# LED_Chaser.net
KiCad netlist of a schematic drawn in Altium Designer
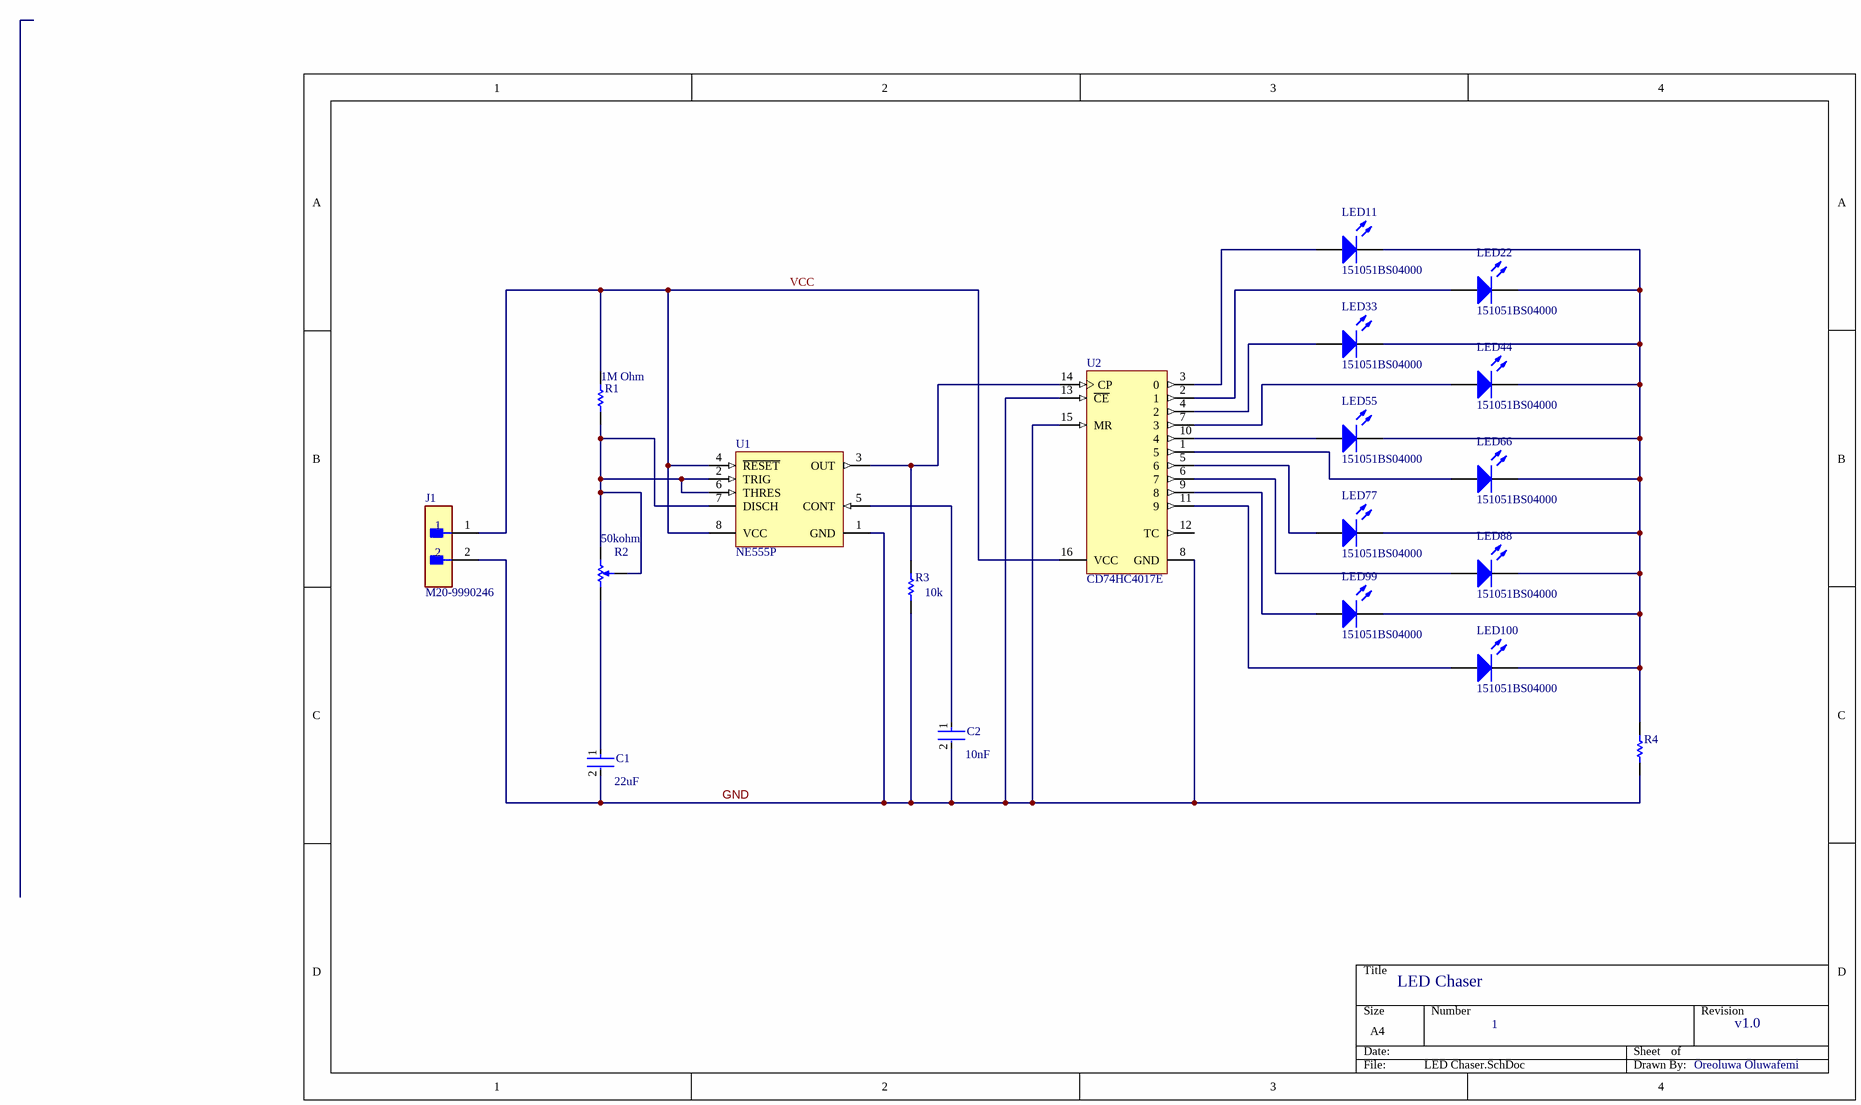
[diagram p0: LED Chaser.SchDoc]

(export (version "E")
  (design (tool "Eeschema 10.0.6"))
  (components
    (comp (ref "C1")
      (value "RCER71E226MWM1H03A")
      (footprint "FP-RCEWM1-MFG")
      (description "CAP CER 22UF 25V X7R RADIAL")
      (fields (field (name "CAPACITANCE") "22uF") (field (name "TOLERANCE") "20%"))
      (libsource (lib "Altium Content Vault") (part "02cd4be3c70576c341d710602a673aa"))
    )
    (comp (ref "C2")
      (value "RCER71E226MWM1H03A")
      (footprint "FP-RCEWM1-MFG")
      (description "CAP CER 22UF 25V X7R RADIAL")
      (fields (field (name "CAPACITANCE") "10nF") (field (name "TOLERANCE") "20%"))
      (libsource (lib "Altium Content Vault") (part "02cd4be3c70576c341d710602a673aa"))
    )
    (comp (ref "J1")
      (value "M20-9990246")
      (footprint "FP-M20-9990246-MFG")
      (description "CONN HEADER VERT 2POS 2.54MM")
      (fields
        (field (name "OCTOPART") "https://octopart.com/m20-9990246-harwin-2590635")
        (field (name "MANUFACTURER") "Harwin")
      )
      (libsource (lib "Altium Content Vault") (part "3bc925449376181038e59eaffc5286c"))
    )
    (comp (ref "LED11")
      (value "151051BS04000")
      (footprint "Type 5mm")
      (description "THT LED round mono-color color lens, WL-TMRW, Blue")
      (fields (field (name "MANUFACTURER") "Wuerth Elektronik"))
      (libsource (lib "Altium Content Vault") (part "WE-LED_K1A2-2"))
    )
    (comp (ref "LED22")
      (value "151051BS04000")
      (footprint "Type 5mm")
      (description "THT LED round mono-color color lens, WL-TMRW, Blue")
      (fields (field (name "MANUFACTURER") "Wuerth Elektronik"))
      (libsource (lib "Altium Content Vault") (part "WE-LED_K1A2-2"))
    )
    (comp (ref "LED33")
      (value "151051BS04000")
      (footprint "Type 5mm")
      (description "THT LED round mono-color color lens, WL-TMRW, Blue")
      (fields (field (name "MANUFACTURER") "Wuerth Elektronik"))
      (libsource (lib "Altium Content Vault") (part "WE-LED_K1A2-2"))
    )
    (comp (ref "LED44")
      (value "151051BS04000")
      (footprint "Type 5mm")
      (description "THT LED round mono-color color lens, WL-TMRW, Blue")
      (fields (field (name "MANUFACTURER") "Wuerth Elektronik"))
      (libsource (lib "Altium Content Vault") (part "WE-LED_K1A2-2"))
    )
    (comp (ref "LED55")
      (value "151051BS04000")
      (footprint "Type 5mm")
      (description "THT LED round mono-color color lens, WL-TMRW, Blue")
      (fields (field (name "MANUFACTURER") "Wuerth Elektronik"))
      (libsource (lib "Altium Content Vault") (part "WE-LED_K1A2-2"))
    )
    (comp (ref "LED66")
      (value "151051BS04000")
      (footprint "Type 5mm")
      (description "THT LED round mono-color color lens, WL-TMRW, Blue")
      (fields (field (name "MANUFACTURER") "Wuerth Elektronik"))
      (libsource (lib "Altium Content Vault") (part "WE-LED_K1A2-2"))
    )
    (comp (ref "LED77")
      (value "151051BS04000")
      (footprint "Type 5mm")
      (description "THT LED round mono-color color lens, WL-TMRW, Blue")
      (fields (field (name "MANUFACTURER") "Wuerth Elektronik"))
      (libsource (lib "Altium Content Vault") (part "WE-LED_K1A2-2"))
    )
    (comp (ref "LED88")
      (value "151051BS04000")
      (footprint "Type 5mm")
      (description "THT LED round mono-color color lens, WL-TMRW, Blue")
      (fields (field (name "MANUFACTURER") "Wuerth Elektronik"))
      (libsource (lib "Altium Content Vault") (part "WE-LED_K1A2-2"))
    )
    (comp (ref "LED99")
      (value "151051BS04000")
      (footprint "Type 5mm")
      (description "THT LED round mono-color color lens, WL-TMRW, Blue")
      (fields (field (name "MANUFACTURER") "Wuerth Elektronik"))
      (libsource (lib "Altium Content Vault") (part "WE-LED_K1A2-2"))
    )
    (comp (ref "LED100")
      (value "151051BS04000")
      (footprint "Type 5mm")
      (description "THT LED round mono-color color lens, WL-TMRW, Blue")
      (fields (field (name "MANUFACTURER") "Wuerth Elektronik"))
      (libsource (lib "Altium Content Vault") (part "WE-LED_K1A2-2"))
    )
    (comp (ref "R1")
      (value "MFR-25FBF52-100K")
      (footprint "RESA60-630X240")
      (description "Axial Resistor, 100 KOhm, +/- 1%, 0.25 W, -55 to 155 degC, 2-Pin THD, RoHS, Bulk")
      (fields (field (name "RESISTANCE") "1M Ohm") (field (name "TOLERANCE") "1%"))
      (libsource (lib "Altium Content Vault") (part "RES-2"))
    )
    (comp (ref "R2")
      (value "3313J-1-503E")
      (footprint "BOUR-3313J-1_V")
      (fields (field (name "MANUFACTURER") "Bourns") (field (name "TRACK RESISTANCE") "50kohm"))
      (libsource (lib "Altium Content Vault") (part "RES-ADJ-3_A"))
    )
    (comp (ref "R3")
      (value "OD103JE")
      (footprint "OMTE-RES7X2.5-2")
      (fields
        (field (name "RESISTANCE (OHMS)") "10k")
        (field (name "TOLERANCE") "±5%")
        (field (name "MANUFACTURER") "Ohmite")
      )
      (libsource (lib "Altium Content Vault") (part "RES-2"))
    )
    (comp (ref "R4")
      (value "OD103JE")
      (footprint "OMTE-RES7X2.5-2")
      (fields (field (name "TOLERANCE") "±5%") (field (name "MANUFACTURER") "Ohmite"))
      (libsource (lib "Altium Content Vault") (part "RES-2"))
    )
    (comp (ref "U1")
      (value "NE555P")
      (footprint "P0008A")
      (description "Precision Timer, 4.5 to 16 V, 0 to 70 degC, 8-Pin DIP, Pb-Free, Tube")
      (fields (field (name "MANUFACTURER") "TexasInstruments"))
      (libsource (lib "Altium Content Vault") (part "TI-NE555-P8"))
    )
    (comp (ref "U2")
      (value "CD74HC4017E")
      (footprint "N0016A")
      (description "High Speed CMOS Logic Decade Counter/Divider with 10 Decoded Outputs, N0016A, TUBE")
      (fields
        (field (name "GENERIC PART NUMBER") "CD74HC4017")
        (field (name "MANUFACTURER") "Texas Instruments")
      )
      (libsource (lib "Altium Content Vault") (part "TI-CD74HC4017-16"))
    )
  )
  (nets
    (net (code "1") (name "/GND") (class "Default")
      (node (ref "C1") (pin "2") (pinfunction "2_2") (pintype "passive"))
      (node (ref "C2") (pin "2") (pinfunction "2_2") (pintype "passive"))
      (node (ref "J1") (pin "2") (pinfunction "2_2") (pintype "passive"))
      (node (ref "R3") (pin "1") (pinfunction "1_1") (pintype "passive"))
      (node (ref "R4") (pin "1") (pinfunction "1_1") (pintype "passive"))
      (node (ref "U1") (pin "1") (pinfunction "GND_1") (pintype "power_in"))
      (node (ref "U2") (pin "13") (pinfunction "~{CE}_13") (pintype "input"))
      (node (ref "U2") (pin "15") (pinfunction "MR_15") (pintype "input"))
      (node (ref "U2") (pin "8") (pinfunction "GND_8") (pintype "power_in"))
    )
    (net (code "2") (name "/VCC") (class "Default")
      (node (ref "J1") (pin "1") (pinfunction "1_1") (pintype "passive"))
      (node (ref "R1") (pin "2") (pinfunction "2_2") (pintype "passive"))
      (node (ref "U1") (pin "4") (pinfunction "~{RESET}_4") (pintype "input"))
      (node (ref "U1") (pin "8") (pinfunction "VCC_8") (pintype "power_in"))
      (node (ref "U2") (pin "16") (pinfunction "VCC_16") (pintype "power_in"))
    )
    (net (code "3") (name "Net-(C1-Pad1)") (class "Default")
      (node (ref "C1") (pin "1") (pinfunction "1_1") (pintype "passive"))
      (node (ref "R2") (pin "1") (pinfunction "1_1") (pintype "passive"))
    )
    (net (code "4") (name "Net-(LED11-A)") (class "Default")
      (node (ref "LED11") (pin "2") (pinfunction "A_2") (pintype "passive"))
      (node (ref "U2") (pin "3") (pinfunction "0_3") (pintype "output"))
    )
    (net (code "5") (name "Net-(LED22-A)") (class "Default")
      (node (ref "LED22") (pin "2") (pinfunction "A_2") (pintype "passive"))
      (node (ref "U2") (pin "2") (pinfunction "1_2") (pintype "output"))
    )
    (net (code "6") (name "Net-(LED33-A)") (class "Default")
      (node (ref "LED33") (pin "2") (pinfunction "A_2") (pintype "passive"))
      (node (ref "U2") (pin "4") (pinfunction "2_4") (pintype "output"))
    )
    (net (code "7") (name "Net-(LED44-A)") (class "Default")
      (node (ref "LED44") (pin "2") (pinfunction "A_2") (pintype "passive"))
      (node (ref "U2") (pin "7") (pinfunction "3_7") (pintype "output"))
    )
    (net (code "8") (name "Net-(LED55-A)") (class "Default")
      (node (ref "LED55") (pin "2") (pinfunction "A_2") (pintype "passive"))
      (node (ref "U2") (pin "10") (pinfunction "4_10") (pintype "output"))
    )
    (net (code "9") (name "Net-(LED66-A)") (class "Default")
      (node (ref "LED66") (pin "2") (pinfunction "A_2") (pintype "passive"))
      (node (ref "U2") (pin "1") (pinfunction "5_1") (pintype "output"))
    )
    (net (code "10") (name "Net-(LED77-A)") (class "Default")
      (node (ref "LED77") (pin "2") (pinfunction "A_2") (pintype "passive"))
      (node (ref "U2") (pin "5") (pinfunction "6_5") (pintype "output"))
    )
    (net (code "11") (name "Net-(LED88-A)") (class "Default")
      (node (ref "LED88") (pin "2") (pinfunction "A_2") (pintype "passive"))
      (node (ref "U2") (pin "6") (pinfunction "7_6") (pintype "output"))
    )
    (net (code "12") (name "Net-(LED99-A)") (class "Default")
      (node (ref "LED99") (pin "2") (pinfunction "A_2") (pintype "passive"))
      (node (ref "U2") (pin "9") (pinfunction "8_9") (pintype "output"))
    )
    (net (code "13") (name "Net-(LED100-A)") (class "Default")
      (node (ref "LED100") (pin "2") (pinfunction "A_2") (pintype "passive"))
      (node (ref "U2") (pin "11") (pinfunction "9_11") (pintype "output"))
    )
    (net (code "14") (name "Net-(LED100-K)") (class "Default")
      (node (ref "LED100") (pin "1") (pinfunction "K_1") (pintype "passive"))
      (node (ref "LED11") (pin "1") (pinfunction "K_1") (pintype "passive"))
      (node (ref "LED22") (pin "1") (pinfunction "K_1") (pintype "passive"))
      (node (ref "LED33") (pin "1") (pinfunction "K_1") (pintype "passive"))
      (node (ref "LED44") (pin "1") (pinfunction "K_1") (pintype "passive"))
      (node (ref "LED55") (pin "1") (pinfunction "K_1") (pintype "passive"))
      (node (ref "LED66") (pin "1") (pinfunction "K_1") (pintype "passive"))
      (node (ref "LED77") (pin "1") (pinfunction "K_1") (pintype "passive"))
      (node (ref "LED88") (pin "1") (pinfunction "K_1") (pintype "passive"))
      (node (ref "LED99") (pin "1") (pinfunction "K_1") (pintype "passive"))
      (node (ref "R4") (pin "2") (pinfunction "2_2") (pintype "passive"))
    )
    (net (code "15") (name "Net-(U1-CONT)") (class "Default")
      (node (ref "C2") (pin "1") (pinfunction "1_1") (pintype "passive"))
      (node (ref "U1") (pin "5") (pinfunction "CONT_5") (pintype "input"))
    )
    (net (code "16") (name "Net-(U1-DISCH)") (class "Default")
      (node (ref "R1") (pin "1") (pinfunction "1_1") (pintype "passive"))
      (node (ref "R2") (pin "2") (pinfunction "2_2") (pintype "passive"))
      (node (ref "R2") (pin "3") (pinfunction "3_3") (pintype "passive"))
      (node (ref "U1") (pin "2") (pinfunction "TRIG_2") (pintype "input"))
      (node (ref "U1") (pin "6") (pinfunction "THRES_6") (pintype "input"))
      (node (ref "U1") (pin "7") (pinfunction "DISCH_7") (pintype "open_collector"))
    )
    (net (code "17") (name "Net-(U1-OUT)") (class "Default")
      (node (ref "R3") (pin "2") (pinfunction "2_2") (pintype "passive"))
      (node (ref "U1") (pin "3") (pinfunction "OUT_3") (pintype "output"))
      (node (ref "U2") (pin "14") (pinfunction "CP_14") (pintype "input"))
    )
    (net (code "18") (name "unconnected-(U2-TC-Pad12)") (class "Default")
      (node (ref "U2") (pin "12") (pinfunction "TC_12") (pintype "output"))
    )
  )
)
